# simple-loop-v2.net
KiCad netlist of a schematic drawn in EAGLE
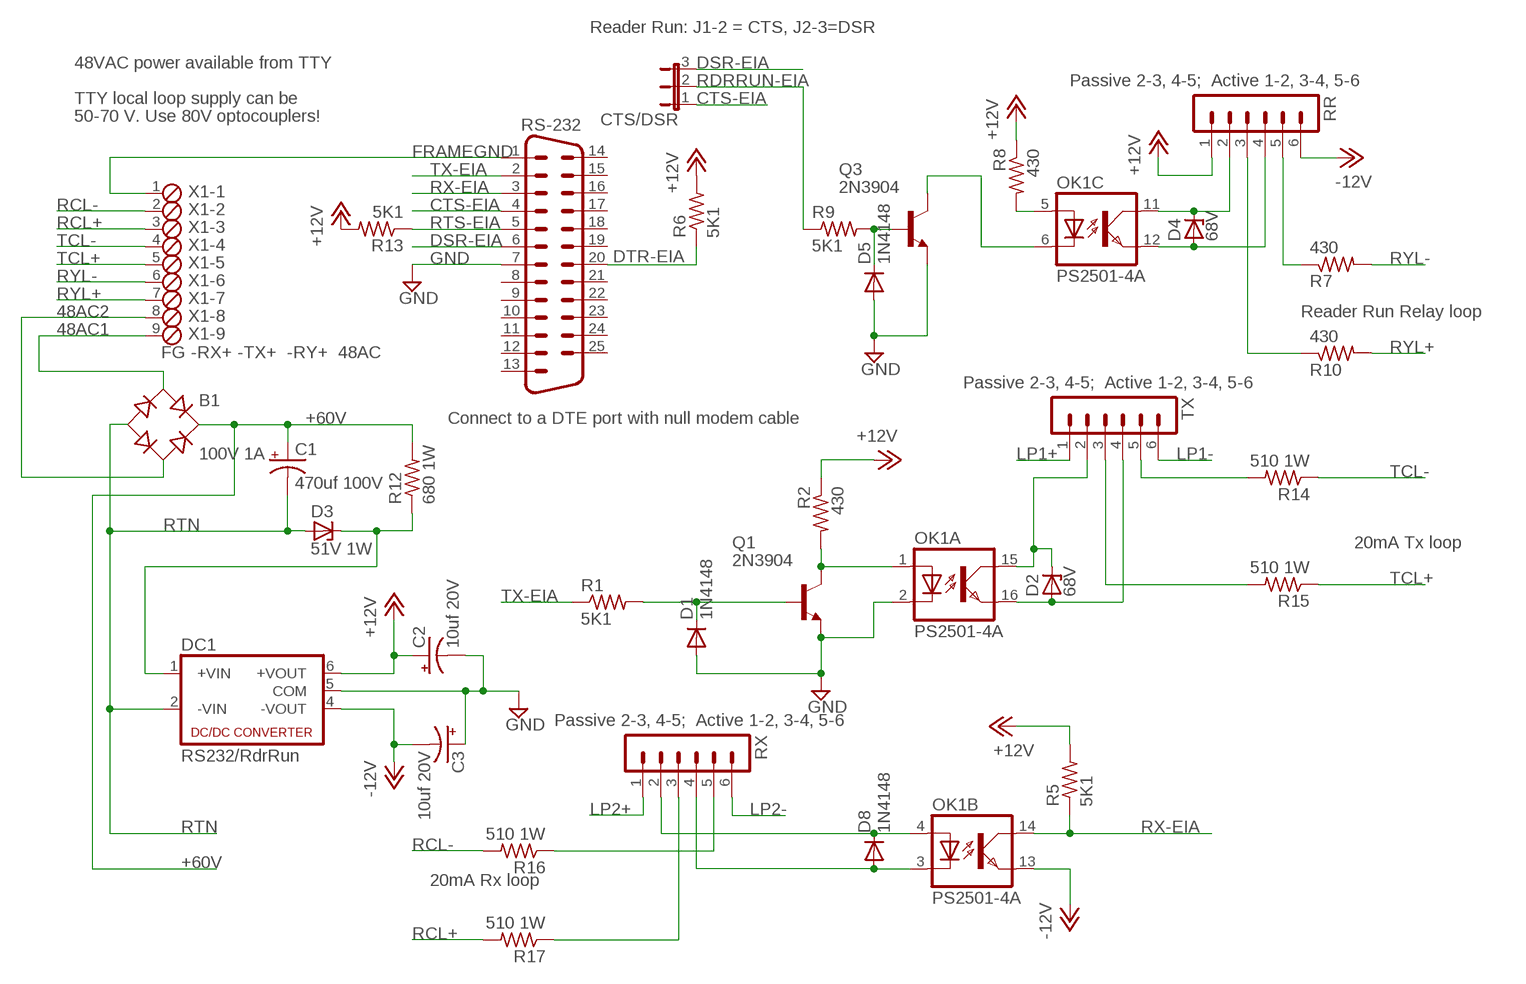
[diagram p0: schematic, sheet 1]
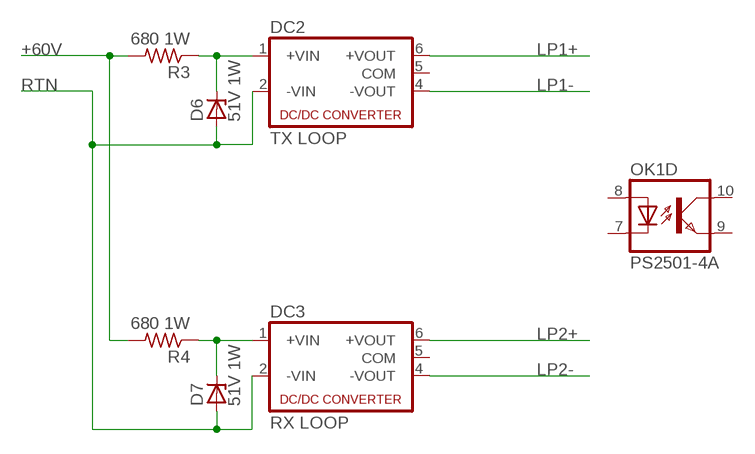
[diagram p1: schematic, sheet 2]

(export (version "E")
  (design (tool "Eeschema 10.0.6"))
  (components
    (comp (ref "B1")
      (value "100V 1A")
      (footprint "eagle-import:RB1A")
      (libsource (lib "eagle-import") (part "RB1A"))
    )
    (comp (ref "C1")
      (value "470uf 100V")
      (footprint "eagle-import:E7,5-18")
      (libsource (lib "eagle-import") (part "CPOL-USE7.5-18"))
    )
    (comp (ref "C2")
      (value "10uf 20V")
      (footprint "eagle-import:E2,5-6")
      (libsource (lib "eagle-import") (part "CPOL-USE2.5-6"))
    )
    (comp (ref "C3")
      (value "10uf 20V")
      (footprint "eagle-import:E2,5-6")
      (libsource (lib "eagle-import") (part "CPOL-USE2.5-6"))
    )
    (comp (ref "CTS/DSR")
      (value "JP2E")
      (footprint "eagle-import:JP2")
      (libsource (lib "eagle-import") (part "JP2E"))
    )
    (comp (ref "D1")
      (value "1N4148")
      (footprint "eagle-import:DO35-10")
      (libsource (lib "eagle-import") (part "1N4148DO35-10"))
    )
    (comp (ref "D2")
      (value "68V")
      (footprint "eagle-import:DO41Z10")
      (libsource (lib "eagle-import") (part "ZENER-DIODEDO41Z10"))
    )
    (comp (ref "D3")
      (value "51V 1W")
      (footprint "eagle-import:DO41Z10")
      (libsource (lib "eagle-import") (part "ZENER-DIODEDO41Z10"))
    )
    (comp (ref "D4")
      (value "68V")
      (footprint "eagle-import:DO41Z10")
      (libsource (lib "eagle-import") (part "ZENER-DIODEDO41Z10"))
    )
    (comp (ref "D5")
      (value "1N4148")
      (footprint "eagle-import:DO35-10")
      (libsource (lib "eagle-import") (part "1N4148DO35-10"))
    )
    (comp (ref "D8")
      (value "1N4148")
      (footprint "eagle-import:DO35-10")
      (libsource (lib "eagle-import") (part "1N4148DO35-10"))
    )
    (comp (ref "DC1")
      (value "RS232/RdrRun")
      (footprint "eagle-import:NMA")
      (fields (field (name "MF") "C & D TECHNOLOGIES, INC") (field (name "MPN") "NMA0515SC"))
      (libsource (lib "eagle-import") (part "NMA"))
    )
    (comp (ref "OK1")
      (value "PS2501-4A")
      (footprint "eagle-import:DIL16")
      (fields (field (name "MF") "VISHAY/TELEFUNKEN") (field (name "MPN") "ILQ1"))
      (libsource (lib "eagle-import") (part "ILQ1"))
    )
    (comp (ref "Q1")
      (value "2N3904")
      (footprint "eagle-import:TO92")
      (libsource (lib "eagle-import") (part "2N3904"))
    )
    (comp (ref "Q3")
      (value "2N3904")
      (footprint "eagle-import:TO92")
      (libsource (lib "eagle-import") (part "2N3904"))
    )
    (comp (ref "R1")
      (value "5K1")
      (footprint "eagle-import:0207_10")
      (libsource (lib "eagle-import") (part "R-US_0207/10"))
    )
    (comp (ref "R2")
      (value "430")
      (footprint "eagle-import:0207_10")
      (libsource (lib "eagle-import") (part "R-US_0207/10"))
    )
    (comp (ref "R5")
      (value "5K1")
      (footprint "eagle-import:0207_10")
      (libsource (lib "eagle-import") (part "R-US_0207/10"))
    )
    (comp (ref "R6")
      (value "5K1")
      (footprint "eagle-import:0207_10")
      (libsource (lib "eagle-import") (part "R-US_0207/10"))
    )
    (comp (ref "R7")
      (value "430")
      (footprint "eagle-import:0207_10")
      (libsource (lib "eagle-import") (part "R-US_0207/10"))
    )
    (comp (ref "R8")
      (value "430")
      (footprint "eagle-import:0207_10")
      (libsource (lib "eagle-import") (part "R-US_0207/10"))
    )
    (comp (ref "R9")
      (value "5K1")
      (footprint "eagle-import:0207_10")
      (libsource (lib "eagle-import") (part "R-US_0207/10"))
    )
    (comp (ref "R10")
      (value "430")
      (footprint "eagle-import:0207_10")
      (libsource (lib "eagle-import") (part "R-US_0207/10"))
    )
    (comp (ref "R12")
      (value "680 1W")
      (footprint "eagle-import:P0817V")
      (libsource (lib "eagle-import") (part "R-US_0817/7V"))
    )
    (comp (ref "R13")
      (value "5K1")
      (footprint "eagle-import:0207_10")
      (libsource (lib "eagle-import") (part "R-US_0207/10"))
    )
    (comp (ref "R14")
      (value "510 1W")
      (footprint "eagle-import:P0817V")
      (libsource (lib "eagle-import") (part "R-US_0817/7V"))
    )
    (comp (ref "R15")
      (value "510 1W")
      (footprint "eagle-import:P0817V")
      (libsource (lib "eagle-import") (part "R-US_0817/7V"))
    )
    (comp (ref "R16")
      (value "510 1W")
      (footprint "eagle-import:P0817V")
      (libsource (lib "eagle-import") (part "R-US_0817/7V"))
    )
    (comp (ref "R17")
      (value "510 1W")
      (footprint "eagle-import:P0817V")
      (libsource (lib "eagle-import") (part "R-US_0817/7V"))
    )
    (comp (ref "RR")
      (value "MA06-1")
      (footprint "eagle-import:MA06-1")
      (libsource (lib "eagle-import") (part "MA06-1"))
    )
    (comp (ref "RS-232")
      (value "M25H")
      (footprint "eagle-import:M25H")
      (libsource (lib "eagle-import") (part "M25H"))
    )
    (comp (ref "RX")
      (value "MA06-1")
      (footprint "eagle-import:MA06-1")
      (libsource (lib "eagle-import") (part "MA06-1"))
    )
    (comp (ref "TX")
      (value "MA06-1")
      (footprint "eagle-import:MA06-1")
      (libsource (lib "eagle-import") (part "MA06-1"))
    )
    (comp (ref "X1")
      (value "FG -RX+ -TX+ -RY+ 48AC")
      (footprint "eagle-import:9POL254")
      (libsource (lib "eagle-import") (part "MPT9"))
    )
    (comp (ref "D6")
      (value "51V 1W")
      (footprint "eagle-import:DO41Z10")
      (libsource (lib "eagle-import") (part "ZENER-DIODEDO41Z10"))
    )
    (comp (ref "D7")
      (value "51V 1W")
      (footprint "eagle-import:DO41Z10")
      (libsource (lib "eagle-import") (part "ZENER-DIODEDO41Z10"))
    )
    (comp (ref "DC2")
      (value "TX LOOP")
      (footprint "eagle-import:NMA")
      (fields (field (name "MF") "C & D TECHNOLOGIES, INC") (field (name "MPN") "NMA0515SC"))
      (libsource (lib "eagle-import") (part "NMA"))
    )
    (comp (ref "DC3")
      (value "RX LOOP")
      (footprint "eagle-import:NMA")
      (fields (field (name "MF") "C & D TECHNOLOGIES, INC") (field (name "MPN") "NMA0515SC"))
      (libsource (lib "eagle-import") (part "NMA"))
    )
    (comp (ref "R3")
      (value "680 1W")
      (footprint "eagle-import:P0817V")
      (libsource (lib "eagle-import") (part "R-US_0817/7V"))
    )
    (comp (ref "R4")
      (value "680 1W")
      (footprint "eagle-import:P0817V")
      (libsource (lib "eagle-import") (part "R-US_0817/7V"))
    )
  )
  (nets
    (net (code "1") (name "+12V") (class "Default")
      (node (ref "C2") (pin "+") (pinfunction "+_+") (pintype "passive"))
      (node (ref "DC1") (pin "6") (pinfunction "+VOUT_6") (pintype "passive"))
      (node (ref "R13") (pin "2") (pinfunction "2_2") (pintype "passive"))
      (node (ref "R2") (pin "1") (pinfunction "1_1") (pintype "passive"))
      (node (ref "R5") (pin "2") (pinfunction "2_2") (pintype "passive"))
      (node (ref "R6") (pin "2") (pinfunction "2_2") (pintype "passive"))
      (node (ref "R8") (pin "1") (pinfunction "1_1") (pintype "passive"))
      (node (ref "RR") (pin "1") (pinfunction "1_1") (pintype "passive"))
    )
    (net (code "2") (name "+60V") (class "Default")
      (node (ref "B1") (pin "+") (pinfunction "+_+") (pintype "passive"))
      (node (ref "C1") (pin "+") (pinfunction "+_+") (pintype "passive"))
      (node (ref "R12") (pin "2") (pinfunction "2_2") (pintype "passive"))
      (node (ref "R3") (pin "2") (pinfunction "2_2") (pintype "passive"))
      (node (ref "R4") (pin "2") (pinfunction "2_2") (pintype "passive"))
    )
    (net (code "3") (name "-12V") (class "Default")
      (node (ref "C3") (pin "-") (pinfunction "-_-") (pintype "passive"))
      (node (ref "DC1") (pin "4") (pinfunction "-VOUT_4") (pintype "passive"))
      (node (ref "OK1") (pin "13") (pinfunction "EMIT_13") (pintype "passive"))
      (node (ref "RR") (pin "6") (pinfunction "6_6") (pintype "passive"))
    )
    (net (code "4") (name "48AC1") (class "Default")
      (node (ref "B1") (pin "AC1") (pinfunction "AC1_AC1") (pintype "passive"))
      (node (ref "X1") (pin "9") (pinfunction "1_9") (pintype "passive"))
    )
    (net (code "5") (name "48AC2") (class "Default")
      (node (ref "B1") (pin "AC2") (pinfunction "AC2_AC2") (pintype "passive"))
      (node (ref "X1") (pin "8") (pinfunction "1_8") (pintype "passive"))
    )
    (net (code "6") (name "CTS-EIA") (class "Default")
      (node (ref "CTS/DSR") (pin "1") (pinfunction "1_1") (pintype "passive"))
      (node (ref "RS-232") (pin "4") (pinfunction "4_4") (pintype "passive"))
    )
    (net (code "7") (name "DSR-EIA") (class "Default")
      (node (ref "CTS/DSR") (pin "3") (pinfunction "3_3") (pintype "passive"))
      (node (ref "RS-232") (pin "6") (pinfunction "6_6") (pintype "passive"))
    )
    (net (code "8") (name "DTR-EIA") (class "Default")
      (node (ref "R6") (pin "1") (pinfunction "1_1") (pintype "passive"))
      (node (ref "RS-232") (pin "20") (pinfunction "20_20") (pintype "passive"))
    )
    (net (code "9") (name "FRAMEGND") (class "Default")
      (node (ref "RS-232") (pin "1") (pinfunction "1_1") (pintype "passive"))
      (node (ref "X1") (pin "1") (pinfunction "1_1") (pintype "passive"))
    )
    (net (code "10") (name "GND") (class "Default")
      (node (ref "C2") (pin "-") (pinfunction "-_-") (pintype "passive"))
      (node (ref "C3") (pin "+") (pinfunction "+_+") (pintype "passive"))
      (node (ref "D1") (pin "A") (pinfunction "A_A") (pintype "passive"))
      (node (ref "D5") (pin "A") (pinfunction "A_A") (pintype "passive"))
      (node (ref "DC1") (pin "5") (pinfunction "COM_5") (pintype "passive"))
      (node (ref "OK1") (pin "2") (pinfunction "C_2") (pintype "passive"))
      (node (ref "Q1") (pin "3") (pinfunction "E_3") (pintype "passive"))
      (node (ref "Q3") (pin "3") (pinfunction "E_3") (pintype "passive"))
      (node (ref "RS-232") (pin "7") (pinfunction "7_7") (pintype "passive"))
    )
    (net (code "11") (name "LP1+") (class "Default")
      (node (ref "DC2") (pin "6") (pinfunction "+VOUT_6") (pintype "passive"))
      (node (ref "TX") (pin "1") (pinfunction "1_1") (pintype "passive"))
    )
    (net (code "12") (name "LP1-") (class "Default")
      (node (ref "DC2") (pin "4") (pinfunction "-VOUT_4") (pintype "passive"))
      (node (ref "TX") (pin "6") (pinfunction "6_6") (pintype "passive"))
    )
    (net (code "13") (name "LP2+") (class "Default")
      (node (ref "DC3") (pin "6") (pinfunction "+VOUT_6") (pintype "passive"))
      (node (ref "RX") (pin "1") (pinfunction "1_1") (pintype "passive"))
    )
    (net (code "14") (name "LP2-") (class "Default")
      (node (ref "DC3") (pin "4") (pinfunction "-VOUT_4") (pintype "passive"))
      (node (ref "RX") (pin "6") (pinfunction "6_6") (pintype "passive"))
    )
    (net (code "15") (name "Net-(DC1-+VIN)") (class "Default")
      (node (ref "D3") (pin "C") (pinfunction "C_C") (pintype "passive"))
      (node (ref "DC1") (pin "1") (pinfunction "+VIN_1") (pintype "passive"))
      (node (ref "R12") (pin "1") (pinfunction "1_1") (pintype "passive"))
    )
    (net (code "16") (name "Net-(DC2-+VIN)") (class "Default")
      (node (ref "D6") (pin "C") (pinfunction "C_C") (pintype "passive"))
      (node (ref "DC2") (pin "1") (pinfunction "+VIN_1") (pintype "passive"))
      (node (ref "R3") (pin "1") (pinfunction "1_1") (pintype "passive"))
    )
    (net (code "17") (name "Net-(DC3-+VIN)") (class "Default")
      (node (ref "D7") (pin "C") (pinfunction "C_C") (pintype "passive"))
      (node (ref "DC3") (pin "1") (pinfunction "+VIN_1") (pintype "passive"))
      (node (ref "R4") (pin "1") (pinfunction "1_1") (pintype "passive"))
    )
    (net (code "18") (name "Net-(OK1A-A)") (class "Default")
      (node (ref "OK1") (pin "1") (pinfunction "A_1") (pintype "passive"))
      (node (ref "Q1") (pin "1") (pinfunction "C_1") (pintype "passive"))
      (node (ref "R2") (pin "2") (pinfunction "2_2") (pintype "passive"))
    )
    (net (code "19") (name "Net-(OK1A-COL)") (class "Default")
      (node (ref "D2") (pin "C") (pinfunction "C_C") (pintype "passive"))
      (node (ref "OK1") (pin "15") (pinfunction "COL_15") (pintype "passive"))
      (node (ref "TX") (pin "2") (pinfunction "2_2") (pintype "passive"))
    )
    (net (code "20") (name "Net-(OK1A-EMIT)") (class "Default")
      (node (ref "D2") (pin "A") (pinfunction "A_A") (pintype "passive"))
      (node (ref "OK1") (pin "16") (pinfunction "EMIT_16") (pintype "passive"))
      (node (ref "TX") (pin "4") (pinfunction "4_4") (pintype "passive"))
    )
    (net (code "21") (name "Net-(OK1B-A)") (class "Default")
      (node (ref "D8") (pin "C") (pinfunction "C_C") (pintype "passive"))
      (node (ref "OK1") (pin "4") (pinfunction "A_4") (pintype "passive"))
      (node (ref "RX") (pin "2") (pinfunction "2_2") (pintype "passive"))
    )
    (net (code "22") (name "Net-(OK1B-C)") (class "Default")
      (node (ref "D8") (pin "A") (pinfunction "A_A") (pintype "passive"))
      (node (ref "OK1") (pin "3") (pinfunction "C_3") (pintype "passive"))
      (node (ref "RX") (pin "4") (pinfunction "4_4") (pintype "passive"))
    )
    (net (code "23") (name "Net-(OK1C-A)") (class "Default")
      (node (ref "OK1") (pin "5") (pinfunction "A_5") (pintype "passive"))
      (node (ref "R8") (pin "2") (pinfunction "2_2") (pintype "passive"))
    )
    (net (code "24") (name "Net-(OK1C-C)") (class "Default")
      (node (ref "OK1") (pin "6") (pinfunction "C_6") (pintype "passive"))
      (node (ref "Q3") (pin "1") (pinfunction "C_1") (pintype "passive"))
    )
    (net (code "25") (name "Net-(OK1C-COL)") (class "Default")
      (node (ref "D4") (pin "C") (pinfunction "C_C") (pintype "passive"))
      (node (ref "OK1") (pin "11") (pinfunction "COL_11") (pintype "passive"))
      (node (ref "RR") (pin "2") (pinfunction "2_2") (pintype "passive"))
    )
    (net (code "26") (name "Net-(OK1C-EMIT)") (class "Default")
      (node (ref "D4") (pin "A") (pinfunction "A_A") (pintype "passive"))
      (node (ref "OK1") (pin "12") (pinfunction "EMIT_12") (pintype "passive"))
      (node (ref "RR") (pin "4") (pinfunction "4_4") (pintype "passive"))
    )
    (net (code "27") (name "Net-(Q1-B)") (class "Default")
      (node (ref "D1") (pin "C") (pinfunction "C_C") (pintype "passive"))
      (node (ref "Q1") (pin "2") (pinfunction "B_2") (pintype "passive"))
      (node (ref "R1") (pin "2") (pinfunction "2_2") (pintype "passive"))
    )
    (net (code "28") (name "Net-(Q3-B)") (class "Default")
      (node (ref "D5") (pin "C") (pinfunction "C_C") (pintype "passive"))
      (node (ref "Q3") (pin "2") (pinfunction "B_2") (pintype "passive"))
      (node (ref "R9") (pin "2") (pinfunction "2_2") (pintype "passive"))
    )
    (net (code "29") (name "Net-(R7-Pad1)") (class "Default")
      (node (ref "R7") (pin "1") (pinfunction "1_1") (pintype "passive"))
      (node (ref "RR") (pin "5") (pinfunction "5_5") (pintype "passive"))
    )
    (net (code "30") (name "Net-(R10-Pad1)") (class "Default")
      (node (ref "R10") (pin "1") (pinfunction "1_1") (pintype "passive"))
      (node (ref "RR") (pin "3") (pinfunction "3_3") (pintype "passive"))
    )
    (net (code "31") (name "Net-(R14-Pad2)") (class "Default")
      (node (ref "R14") (pin "2") (pinfunction "2_2") (pintype "passive"))
      (node (ref "TX") (pin "5") (pinfunction "5_5") (pintype "passive"))
    )
    (net (code "32") (name "Net-(R15-Pad2)") (class "Default")
      (node (ref "R15") (pin "2") (pinfunction "2_2") (pintype "passive"))
      (node (ref "TX") (pin "3") (pinfunction "3_3") (pintype "passive"))
    )
    (net (code "33") (name "Net-(R16-Pad1)") (class "Default")
      (node (ref "R16") (pin "1") (pinfunction "1_1") (pintype "passive"))
      (node (ref "RX") (pin "5") (pinfunction "5_5") (pintype "passive"))
    )
    (net (code "34") (name "Net-(R17-Pad1)") (class "Default")
      (node (ref "R17") (pin "1") (pinfunction "1_1") (pintype "passive"))
      (node (ref "RX") (pin "3") (pinfunction "3_3") (pintype "passive"))
    )
    (net (code "35") (name "RCL+") (class "Default")
      (node (ref "R17") (pin "2") (pinfunction "2_2") (pintype "passive"))
      (node (ref "X1") (pin "3") (pinfunction "1_3") (pintype "passive"))
    )
    (net (code "36") (name "RCL-") (class "Default")
      (node (ref "R16") (pin "2") (pinfunction "2_2") (pintype "passive"))
      (node (ref "X1") (pin "2") (pinfunction "1_2") (pintype "passive"))
    )
    (net (code "37") (name "RDRRUN-EIA") (class "Default")
      (node (ref "CTS/DSR") (pin "2") (pinfunction "2_2") (pintype "passive"))
      (node (ref "R9") (pin "1") (pinfunction "1_1") (pintype "passive"))
    )
    (net (code "38") (name "RTN") (class "Default")
      (node (ref "B1") (pin "-") (pinfunction "-_-") (pintype "passive"))
      (node (ref "C1") (pin "-") (pinfunction "-_-") (pintype "passive"))
      (node (ref "D3") (pin "A") (pinfunction "A_A") (pintype "passive"))
      (node (ref "D6") (pin "A") (pinfunction "A_A") (pintype "passive"))
      (node (ref "D7") (pin "A") (pinfunction "A_A") (pintype "passive"))
      (node (ref "DC1") (pin "2") (pinfunction "-VIN_2") (pintype "passive"))
      (node (ref "DC2") (pin "2") (pinfunction "-VIN_2") (pintype "passive"))
      (node (ref "DC3") (pin "2") (pinfunction "-VIN_2") (pintype "passive"))
    )
    (net (code "39") (name "RTS-EIA") (class "Default")
      (node (ref "R13") (pin "1") (pinfunction "1_1") (pintype "passive"))
      (node (ref "RS-232") (pin "5") (pinfunction "5_5") (pintype "passive"))
    )
    (net (code "40") (name "RX-EIA") (class "Default")
      (node (ref "OK1") (pin "14") (pinfunction "COL_14") (pintype "passive"))
      (node (ref "R5") (pin "1") (pinfunction "1_1") (pintype "passive"))
      (node (ref "RS-232") (pin "3") (pinfunction "3_3") (pintype "passive"))
    )
    (net (code "41") (name "RYL+") (class "Default")
      (node (ref "R10") (pin "2") (pinfunction "2_2") (pintype "passive"))
      (node (ref "X1") (pin "7") (pinfunction "1_7") (pintype "passive"))
    )
    (net (code "42") (name "RYL-") (class "Default")
      (node (ref "R7") (pin "2") (pinfunction "2_2") (pintype "passive"))
      (node (ref "X1") (pin "6") (pinfunction "1_6") (pintype "passive"))
    )
    (net (code "43") (name "TCL+") (class "Default")
      (node (ref "R15") (pin "1") (pinfunction "1_1") (pintype "passive"))
      (node (ref "X1") (pin "5") (pinfunction "1_5") (pintype "passive"))
    )
    (net (code "44") (name "TCL-") (class "Default")
      (node (ref "R14") (pin "1") (pinfunction "1_1") (pintype "passive"))
      (node (ref "X1") (pin "4") (pinfunction "1_4") (pintype "passive"))
    )
    (net (code "45") (name "TX-EIA") (class "Default")
      (node (ref "R1") (pin "1") (pinfunction "1_1") (pintype "passive"))
      (node (ref "RS-232") (pin "2") (pinfunction "2_2") (pintype "passive"))
    )
    (net (code "46") (name "unconnected-(DC2-COM-Pad5)") (class "Default")
      (node (ref "DC2") (pin "5") (pinfunction "COM_5") (pintype "passive"))
    )
    (net (code "47") (name "unconnected-(DC3-COM-Pad5)") (class "Default")
      (node (ref "DC3") (pin "5") (pinfunction "COM_5") (pintype "passive"))
    )
    (net (code "48") (name "unconnected-(OK1D-A-Pad8)") (class "Default")
      (node (ref "OK1") (pin "8") (pinfunction "A_8") (pintype "passive"))
    )
    (net (code "49") (name "unconnected-(OK1D-C-Pad7)") (class "Default")
      (node (ref "OK1") (pin "7") (pinfunction "C_7") (pintype "passive"))
    )
    (net (code "50") (name "unconnected-(OK1D-COL-Pad10)") (class "Default")
      (node (ref "OK1") (pin "10") (pinfunction "COL_10") (pintype "passive"))
    )
    (net (code "51") (name "unconnected-(OK1D-EMIT-Pad9)") (class "Default")
      (node (ref "OK1") (pin "9") (pinfunction "EMIT_9") (pintype "passive"))
    )
    (net (code "52") (name "unconnected-(RS-232-Pad8)") (class "Default")
      (node (ref "RS-232") (pin "8") (pinfunction "8_8") (pintype "passive"))
    )
    (net (code "53") (name "unconnected-(RS-232-Pad9)") (class "Default")
      (node (ref "RS-232") (pin "9") (pinfunction "9_9") (pintype "passive"))
    )
    (net (code "54") (name "unconnected-(RS-232-Pad10)") (class "Default")
      (node (ref "RS-232") (pin "10") (pinfunction "10_10") (pintype "passive"))
    )
    (net (code "55") (name "unconnected-(RS-232-Pad11)") (class "Default")
      (node (ref "RS-232") (pin "11") (pinfunction "11_11") (pintype "passive"))
    )
    (net (code "56") (name "unconnected-(RS-232-Pad12)") (class "Default")
      (node (ref "RS-232") (pin "12") (pinfunction "12_12") (pintype "passive"))
    )
    (net (code "57") (name "unconnected-(RS-232-Pad13)") (class "Default")
      (node (ref "RS-232") (pin "13") (pinfunction "13_13") (pintype "passive"))
    )
    (net (code "58") (name "unconnected-(RS-232-Pad14)") (class "Default")
      (node (ref "RS-232") (pin "14") (pinfunction "14_14") (pintype "passive"))
    )
    (net (code "59") (name "unconnected-(RS-232-Pad15)") (class "Default")
      (node (ref "RS-232") (pin "15") (pinfunction "15_15") (pintype "passive"))
    )
    (net (code "60") (name "unconnected-(RS-232-Pad16)") (class "Default")
      (node (ref "RS-232") (pin "16") (pinfunction "16_16") (pintype "passive"))
    )
    (net (code "61") (name "unconnected-(RS-232-Pad17)") (class "Default")
      (node (ref "RS-232") (pin "17") (pinfunction "17_17") (pintype "passive"))
    )
    (net (code "62") (name "unconnected-(RS-232-Pad18)") (class "Default")
      (node (ref "RS-232") (pin "18") (pinfunction "18_18") (pintype "passive"))
    )
    (net (code "63") (name "unconnected-(RS-232-Pad19)") (class "Default")
      (node (ref "RS-232") (pin "19") (pinfunction "19_19") (pintype "passive"))
    )
    (net (code "64") (name "unconnected-(RS-232-Pad21)") (class "Default")
      (node (ref "RS-232") (pin "21") (pinfunction "21_21") (pintype "passive"))
    )
    (net (code "65") (name "unconnected-(RS-232-Pad22)") (class "Default")
      (node (ref "RS-232") (pin "22") (pinfunction "22_22") (pintype "passive"))
    )
    (net (code "66") (name "unconnected-(RS-232-Pad23)") (class "Default")
      (node (ref "RS-232") (pin "23") (pinfunction "23_23") (pintype "passive"))
    )
    (net (code "67") (name "unconnected-(RS-232-Pad24)") (class "Default")
      (node (ref "RS-232") (pin "24") (pinfunction "24_24") (pintype "passive"))
    )
    (net (code "68") (name "unconnected-(RS-232-Pad25)") (class "Default")
      (node (ref "RS-232") (pin "25") (pinfunction "25_25") (pintype "passive"))
    )
  )
)
